# 08_-_ETHERNET.net
KiCad netlist of a schematic drawn in Altium Designer
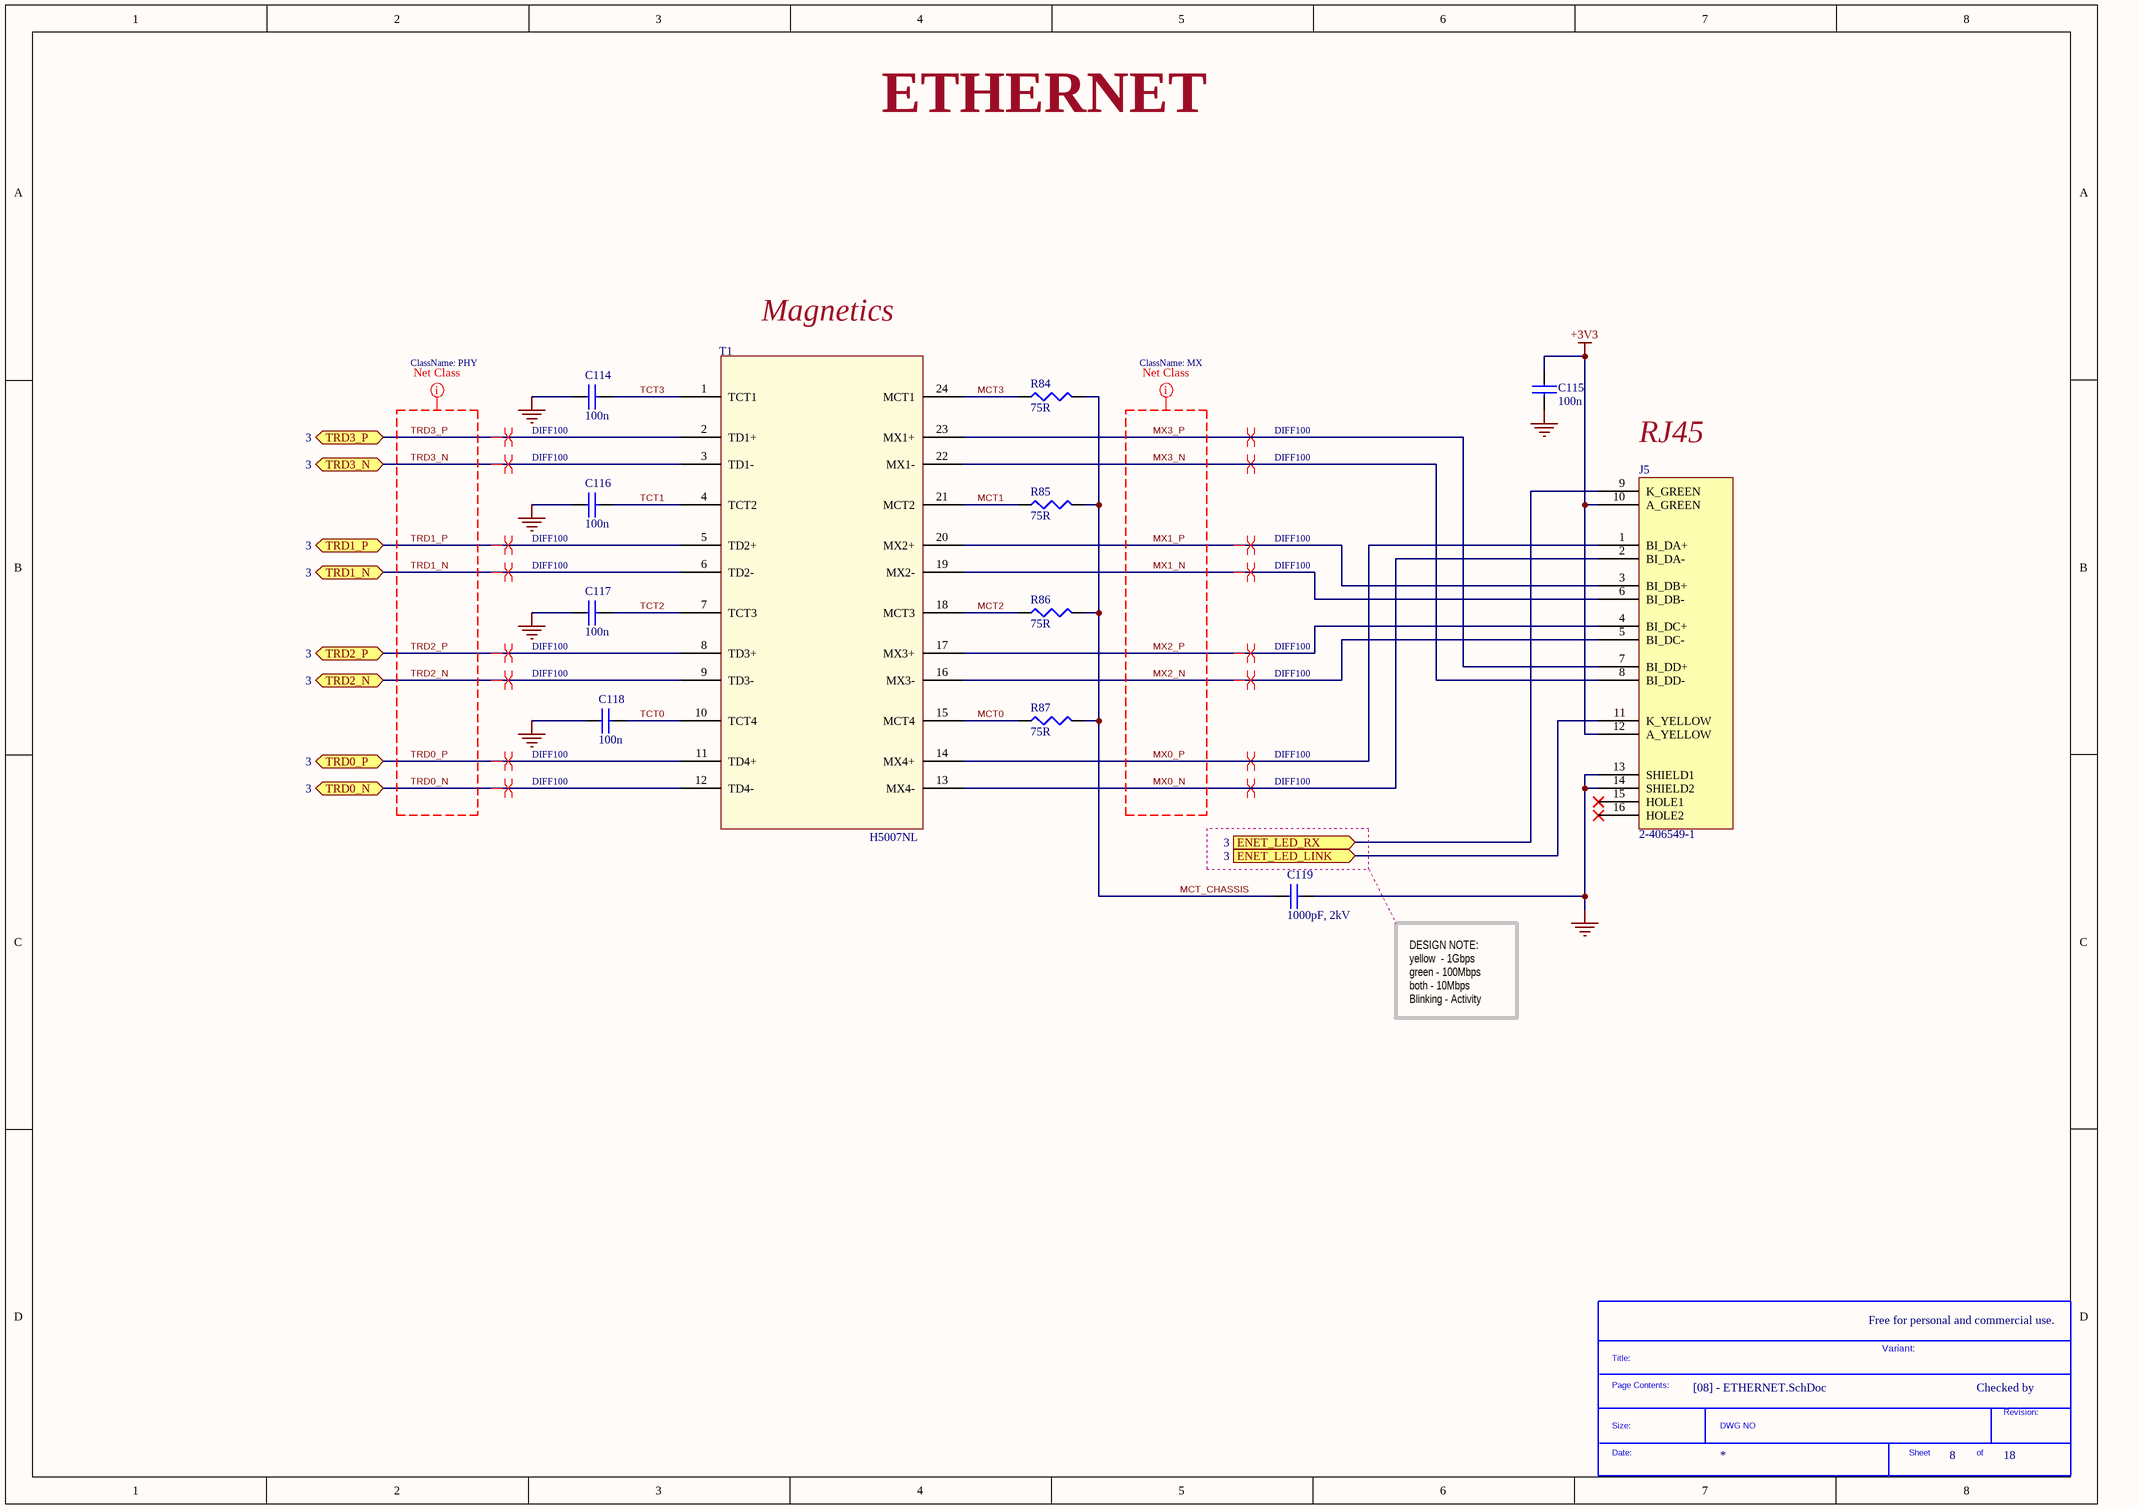
[diagram p0: [08] - ETHERNET.SchDoc]

(export (version "E")
  (design (tool "Eeschema 10.0.6"))
  (components
    (comp (ref "*") (value "SDTitleBlock") (libsource (lib "*") (part "SDTitleBlock")))
    (comp (ref "C114")
      (value "100n")
      (footprint "C0402")
      (description "CAP CER .10UF 50V X5R 10% 0402")
      (fields
        (field (name "MANUFACTURER") "TDK Corporation")
        (field (name "MANUFACTURER PART NUMBER") "C1005X5R1H104K")
      )
      (libsource (lib "Integrated_Library_FEDEVEL_APR_2015") (part "C1005X5R1H104K"))
    )
    (comp (ref "C115")
      (value "100n")
      (footprint "C0402")
      (description "CAP CER .10UF 50V X5R 10% 0402")
      (fields
        (field (name "MANUFACTURER") "TDK Corporation")
        (field (name "MANUFACTURER PART NUMBER") "C1005X5R1H104K")
      )
      (libsource (lib "Integrated_Library_FEDEVEL_APR_2015") (part "C1005X5R1H104K"))
    )
    (comp (ref "C116")
      (value "100n")
      (footprint "C0402")
      (description "CAP CER .10UF 50V X5R 10% 0402")
      (fields
        (field (name "MANUFACTURER") "TDK Corporation")
        (field (name "MANUFACTURER PART NUMBER") "C1005X5R1H104K")
      )
      (libsource (lib "Integrated_Library_FEDEVEL_APR_2015") (part "C1005X5R1H104K"))
    )
    (comp (ref "C117")
      (value "100n")
      (footprint "C0402")
      (description "CAP CER .10UF 50V X5R 10% 0402")
      (fields
        (field (name "MANUFACTURER") "TDK Corporation")
        (field (name "MANUFACTURER PART NUMBER") "C1005X5R1H104K")
      )
      (libsource (lib "Integrated_Library_FEDEVEL_APR_2015") (part "C1005X5R1H104K"))
    )
    (comp (ref "C118")
      (value "100n")
      (footprint "C0402")
      (description "CAP CER .10UF 50V X5R 10% 0402")
      (fields
        (field (name "MANUFACTURER") "TDK Corporation")
        (field (name "MANUFACTURER PART NUMBER") "C1005X5R1H104K")
      )
      (libsource (lib "Integrated_Library_FEDEVEL_APR_2015") (part "C1005X5R1H104K"))
    )
    (comp (ref "C119")
      (value "1000pF, 2kV")
      (footprint "C1206")
      (description "CAP CER 1000PF 2000V X7R 1206 FT")
      (fields
        (field (name "MANUFACTURER") "Kemet")
        (field (name "MANUFACTURER PART NUMBER") "C1206X102KGRACTU")
      )
      (libsource (lib "Integrated_Library_FEDEVEL_APR_2015") (part "C1206X102KGRACTU"))
    )
    (comp (ref "J5")
      (value "2-406549-1")
      (footprint "RJ45LED")
      (description "CONN MOD JACK 8POS R/A G-Y PCB")
      (fields (field (name "MANUFACTURER") "Tyco"))
      (libsource (lib "Integrated_Library_FEDEVEL_APR_2015") (part "2-406549-1"))
    )
    (comp (ref "R84")
      (value "75R")
      (footprint "R0402")
      (description "RES 75.0 OHM 1/16W 1% 0402 SMD")
      (fields
        (field (name "MANUFACTURER") "Yageo")
        (field (name "MANUFACTURER PART NUMBER") "RC0402FR-0775RL")
      )
      (libsource (lib "Integrated_Library_FEDEVEL_APR_2015") (part "RC0402FR-0775RL"))
    )
    (comp (ref "R85")
      (value "75R")
      (footprint "R0402")
      (description "RES 75.0 OHM 1/16W 1% 0402 SMD")
      (fields
        (field (name "MANUFACTURER") "Yageo")
        (field (name "MANUFACTURER PART NUMBER") "RC0402FR-0775RL")
      )
      (libsource (lib "Integrated_Library_FEDEVEL_APR_2015") (part "RC0402FR-0775RL"))
    )
    (comp (ref "R86")
      (value "75R")
      (footprint "R0402")
      (description "RES 75.0 OHM 1/16W 1% 0402 SMD")
      (fields
        (field (name "MANUFACTURER") "Yageo")
        (field (name "MANUFACTURER PART NUMBER") "RC0402FR-0775RL")
      )
      (libsource (lib "Integrated_Library_FEDEVEL_APR_2015") (part "RC0402FR-0775RL"))
    )
    (comp (ref "R87")
      (value "75R")
      (footprint "R0402")
      (description "RES 75.0 OHM 1/16W 1% 0402 SMD")
      (fields
        (field (name "MANUFACTURER") "Yageo")
        (field (name "MANUFACTURER PART NUMBER") "RC0402FR-0775RL")
      )
      (libsource (lib "Integrated_Library_FEDEVEL_APR_2015") (part "RC0402FR-0775RL"))
    )
    (comp (ref "T1")
      (value "H5007NL")
      (footprint "H5007NL")
      (description "MODULE SINGLE GIGABIT LAN 24SOIC")
      (fields (field (name "MANUFACTURER") "PULSE ELECTRONICS CORPORATION"))
      (libsource (lib "Integrated_Library_FEDEVEL_APR_2015") (part "H5007NL"))
    )
  )
  (nets
    (net (code "1") (name "+3V3") (class "Default")
      (node (ref "C115") (pin "1") (pinfunction "1_1") (pintype "passive"))
      (node (ref "J5") (pin "10") (pinfunction "A_GREEN_10") (pintype "passive"))
      (node (ref "J5") (pin "12") (pinfunction "A_YELLOW_12") (pintype "passive"))
    )
    (net (code "2") (name "/ENET_LED_LINK") (class "Default")
      (node (ref "J5") (pin "11") (pinfunction "K_YELLOW_11") (pintype "passive"))
    )
    (net (code "3") (name "/ENET_LED_RX") (class "Default")
      (node (ref "J5") (pin "9") (pinfunction "K_GREEN_9") (pintype "passive"))
    )
    (net (code "4") (name "/MCT0") (class "Default")
      (node (ref "R87") (pin "1") (pinfunction "1_1") (pintype "passive"))
      (node (ref "T1") (pin "15") (pinfunction "MCT4_15") (pintype "passive"))
    )
    (net (code "5") (name "/MCT1") (class "Default")
      (node (ref "R85") (pin "1") (pinfunction "1_1") (pintype "passive"))
      (node (ref "T1") (pin "21") (pinfunction "MCT2_21") (pintype "passive"))
    )
    (net (code "6") (name "/MCT2") (class "Default")
      (node (ref "R86") (pin "1") (pinfunction "1_1") (pintype "passive"))
      (node (ref "T1") (pin "18") (pinfunction "MCT3_18") (pintype "passive"))
    )
    (net (code "7") (name "/MCT3") (class "Default")
      (node (ref "R84") (pin "1") (pinfunction "1_1") (pintype "passive"))
      (node (ref "T1") (pin "24") (pinfunction "MCT1_24") (pintype "passive"))
    )
    (net (code "8") (name "/MCT_CHASSIS") (class "Default")
      (node (ref "C119") (pin "1") (pinfunction "1_1") (pintype "passive"))
      (node (ref "R84") (pin "2") (pinfunction "2_2") (pintype "passive"))
      (node (ref "R85") (pin "2") (pinfunction "2_2") (pintype "passive"))
      (node (ref "R86") (pin "2") (pinfunction "2_2") (pintype "passive"))
      (node (ref "R87") (pin "2") (pinfunction "2_2") (pintype "passive"))
    )
    (net (code "9") (name "/MX0_N") (class "Default")
      (node (ref "J5") (pin "2") (pinfunction "BI_DA-_2") (pintype "passive"))
      (node (ref "T1") (pin "13") (pinfunction "MX4-_13") (pintype "passive"))
    )
    (net (code "10") (name "/MX0_P") (class "Default")
      (node (ref "J5") (pin "1") (pinfunction "BI_DA+_1") (pintype "passive"))
      (node (ref "T1") (pin "14") (pinfunction "MX4+_14") (pintype "passive"))
    )
    (net (code "11") (name "/MX1_N") (class "Default")
      (node (ref "J5") (pin "6") (pinfunction "BI_DB-_6") (pintype "passive"))
      (node (ref "T1") (pin "19") (pinfunction "MX2-_19") (pintype "passive"))
    )
    (net (code "12") (name "/MX1_P") (class "Default")
      (node (ref "J5") (pin "3") (pinfunction "BI_DB+_3") (pintype "passive"))
      (node (ref "T1") (pin "20") (pinfunction "MX2+_20") (pintype "passive"))
    )
    (net (code "13") (name "/MX2_N") (class "Default")
      (node (ref "J5") (pin "5") (pinfunction "BI_DC-_5") (pintype "passive"))
      (node (ref "T1") (pin "16") (pinfunction "MX3-_16") (pintype "passive"))
    )
    (net (code "14") (name "/MX2_P") (class "Default")
      (node (ref "J5") (pin "4") (pinfunction "BI_DC+_4") (pintype "passive"))
      (node (ref "T1") (pin "17") (pinfunction "MX3+_17") (pintype "passive"))
    )
    (net (code "15") (name "/MX3_N") (class "Default")
      (node (ref "J5") (pin "8") (pinfunction "BI_DD-_8") (pintype "passive"))
      (node (ref "T1") (pin "22") (pinfunction "MX1-_22") (pintype "passive"))
    )
    (net (code "16") (name "/MX3_P") (class "Default")
      (node (ref "J5") (pin "7") (pinfunction "BI_DD+_7") (pintype "passive"))
      (node (ref "T1") (pin "23") (pinfunction "MX1+_23") (pintype "passive"))
    )
    (net (code "17") (name "/TCT0") (class "Default")
      (node (ref "C118") (pin "2") (pinfunction "2_2") (pintype "passive"))
      (node (ref "T1") (pin "10") (pinfunction "TCT4_10") (pintype "passive"))
    )
    (net (code "18") (name "/TCT1") (class "Default")
      (node (ref "C116") (pin "2") (pinfunction "2_2") (pintype "passive"))
      (node (ref "T1") (pin "4") (pinfunction "TCT2_4") (pintype "passive"))
    )
    (net (code "19") (name "/TCT2") (class "Default")
      (node (ref "C117") (pin "2") (pinfunction "2_2") (pintype "passive"))
      (node (ref "T1") (pin "7") (pinfunction "TCT3_7") (pintype "passive"))
    )
    (net (code "20") (name "/TCT3") (class "Default")
      (node (ref "C114") (pin "2") (pinfunction "2_2") (pintype "passive"))
      (node (ref "T1") (pin "1") (pinfunction "TCT1_1") (pintype "passive"))
    )
    (net (code "21") (name "/TRD0_N") (class "Default")
      (node (ref "T1") (pin "12") (pinfunction "TD4-_12") (pintype "passive"))
    )
    (net (code "22") (name "/TRD0_P") (class "Default")
      (node (ref "T1") (pin "11") (pinfunction "TD4+_11") (pintype "passive"))
    )
    (net (code "23") (name "/TRD1_N") (class "Default")
      (node (ref "T1") (pin "6") (pinfunction "TD2-_6") (pintype "passive"))
    )
    (net (code "24") (name "/TRD1_P") (class "Default")
      (node (ref "T1") (pin "5") (pinfunction "TD2+_5") (pintype "passive"))
    )
    (net (code "25") (name "/TRD2_N") (class "Default")
      (node (ref "T1") (pin "9") (pinfunction "TD3-_9") (pintype "passive"))
    )
    (net (code "26") (name "/TRD2_P") (class "Default")
      (node (ref "T1") (pin "8") (pinfunction "TD3+_8") (pintype "passive"))
    )
    (net (code "27") (name "/TRD3_N") (class "Default")
      (node (ref "T1") (pin "3") (pinfunction "TD1-_3") (pintype "passive"))
    )
    (net (code "28") (name "/TRD3_P") (class "Default")
      (node (ref "T1") (pin "2") (pinfunction "TD1+_2") (pintype "passive"))
    )
    (net (code "29") (name "GND") (class "Default")
      (node (ref "C114") (pin "1") (pinfunction "1_1") (pintype "passive"))
      (node (ref "C115") (pin "2") (pinfunction "2_2") (pintype "passive"))
      (node (ref "C116") (pin "1") (pinfunction "1_1") (pintype "passive"))
      (node (ref "C117") (pin "1") (pinfunction "1_1") (pintype "passive"))
      (node (ref "C118") (pin "1") (pinfunction "1_1") (pintype "passive"))
      (node (ref "C119") (pin "2") (pinfunction "2_2") (pintype "passive"))
      (node (ref "J5") (pin "13") (pinfunction "SHIELD1_13") (pintype "passive"))
      (node (ref "J5") (pin "14") (pinfunction "SHIELD2_14") (pintype "passive"))
    )
    (net (code "30") (name "unconnected-(J5-HOLE1-Pad15)") (class "Default")
      (node (ref "J5") (pin "15") (pinfunction "HOLE1_15") (pintype "passive+no_connect"))
    )
    (net (code "31") (name "unconnected-(J5-HOLE2-Pad16)") (class "Default")
      (node (ref "J5") (pin "16") (pinfunction "HOLE2_16") (pintype "passive+no_connect"))
    )
  )
)
